# Sheet1.net
KiCad netlist of a schematic drawn in Altium Designer
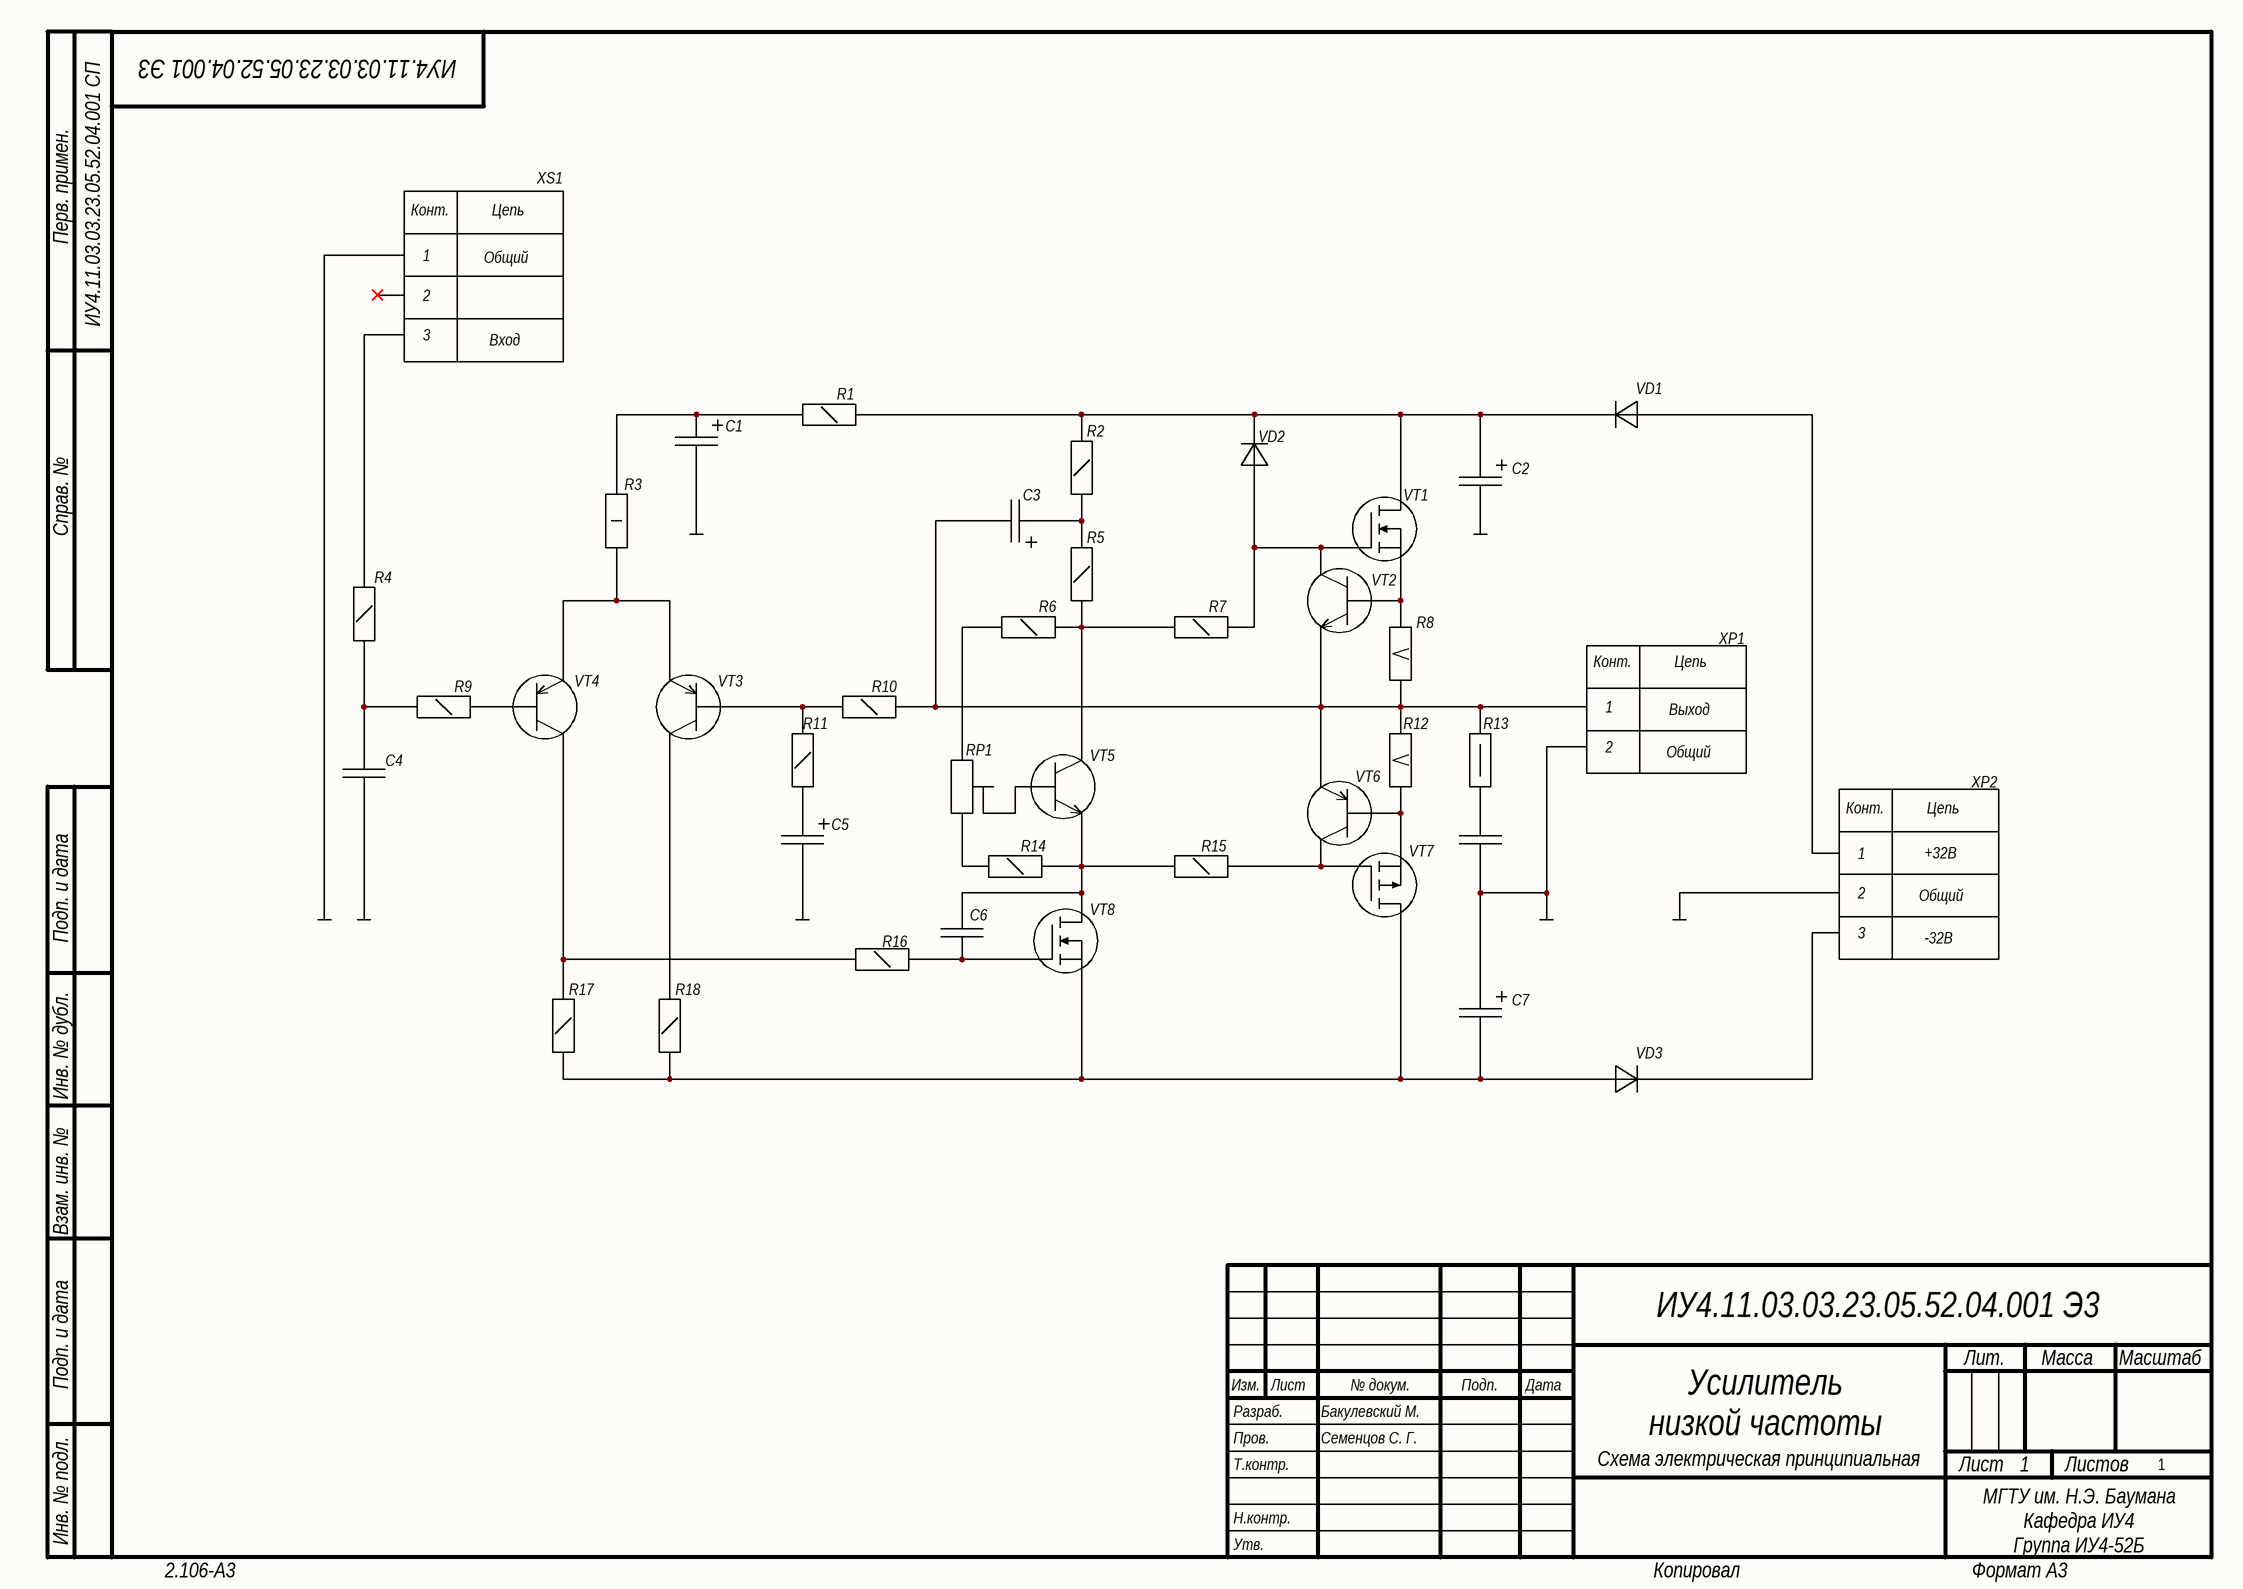
[diagram p0: Sheet1.SchDoc]

(export (version "E")
  (design (tool "Eeschema 10.0.6"))
  (components
    (comp (ref "C1")
      (value "2200uF 35V")
      (footprint "CAPPR350-800X700")
      (libsource (lib "Schlib1") (part "Cap Polarity 47uF 50V"))
    )
    (comp (ref "C2")
      (value "2200uF 35V")
      (footprint "CAPPR750-1600X3150")
      (libsource (lib "Schlib1") (part "Cap Polarity 2200uF 35V"))
    )
    (comp (ref "C3")
      (value "2200uF 35V")
      (footprint "CAPPR350-800X700")
      (libsource (lib "Schlib1") (part "Cap Polarity 47uF 50V"))
    )
    (comp (ref "C4")
      (value "Cap Ceramic 100pF")
      (footprint "CAPRR508-350X500X500")
      (libsource (lib "Schlib1") (part "Cap Ceramic 100pF"))
    )
    (comp (ref "C5")
      (value "100uF 100V")
      (footprint "CAPPR500-1000X2050")
      (libsource (lib "Schlib1") (part "Cap Polarity 100uF 100V"))
    )
    (comp (ref "C6")
      (value "Cap Ceramic 100pF")
      (footprint "CAPRR508-350X500X500")
      (libsource (lib "Schlib1") (part "Cap Ceramic 100pF"))
    )
    (comp (ref "C7")
      (value "2200uF 35V")
      (footprint "CAPPR750-1600X3150")
      (libsource (lib "Schlib1") (part "Cap Polarity 2200uF 35V"))
    )
    (comp (ref "https://www.eetimes.com/ic-audio-power-amplifiers-and-zobel-networks-one-size-does-not-fit-all/1")
      (value "2200uF 35V")
      (footprint "CAPR1000-400X1300X950")
      (libsource (lib "Schlib1") (part "Cap Film 0.68uF 250V"))
    )
    (comp (ref "R1")
      (value "Resistor 0.25W")
      (footprint "RES1016-630X250")
      (libsource (lib "Schlib1") (part "Resistor 0.25W"))
    )
    (comp (ref "R2")
      (value "Resistor 0.25W")
      (footprint "RES1016-630X250")
      (libsource (lib "Schlib1") (part "Resistor 0.25W"))
    )
    (comp (ref "R3")
      (value "Resistor 1W")
      (footprint "RES1651-1000X390")
      (libsource (lib "") (part "Resistor 1W_1"))
    )
    (comp (ref "R4")
      (value "Resistor 0.25W")
      (footprint "RES1016-630X250")
      (libsource (lib "Schlib1") (part "Resistor 0.25W"))
    )
    (comp (ref "R5")
      (value "Resistor 0.25W")
      (footprint "RES1016-630X250")
      (libsource (lib "Schlib1") (part "Resistor 0.25W"))
    )
    (comp (ref "R6")
      (value "Resistor 0.25W")
      (footprint "RES1016-630X250")
      (libsource (lib "Schlib1") (part "Resistor 0.25W"))
    )
    (comp (ref "R7")
      (value "Resistor 0.25W")
      (footprint "RES1016-630X250")
      (libsource (lib "Schlib1") (part "Resistor 0.25W"))
    )
    (comp (ref "R8")
      (value "Resistor 5W")
      (footprint "RES_5W")
      (libsource (lib "Schlib1") (part "Resistor 5W"))
    )
    (comp (ref "R9")
      (value "Resistor 0.25W")
      (footprint "RES1016-630X250")
      (libsource (lib "Schlib1") (part "Resistor 0.25W"))
    )
    (comp (ref "R10")
      (value "Resistor 0.25W")
      (footprint "RES1016-630X250")
      (libsource (lib "Schlib1") (part "Resistor 0.25W"))
    )
    (comp (ref "R11")
      (value "Resistor 0.25W")
      (footprint "RES1016-630X250")
      (libsource (lib "Schlib1") (part "Resistor 0.25W"))
    )
    (comp (ref "R12")
      (value "Resistor 5W")
      (footprint "RES_5W")
      (libsource (lib "Schlib1") (part "Resistor 5W"))
    )
    (comp (ref "R13")
      (value "Resistor 1W")
      (footprint "RES1651-1000X390")
      (libsource (lib "Schlib1") (part "Resistor 1W"))
    )
    (comp (ref "R14")
      (value "Resistor 0.25W")
      (footprint "RES1016-630X250")
      (libsource (lib "Schlib1") (part "Resistor 0.25W"))
    )
    (comp (ref "R15")
      (value "Resistor 0.25W")
      (footprint "RES1016-630X250")
      (libsource (lib "Schlib1") (part "Resistor 0.25W"))
    )
    (comp (ref "R16")
      (value "Resistor 0.25W")
      (footprint "RES1016-630X250")
      (libsource (lib "Schlib1") (part "Resistor 0.25W"))
    )
    (comp (ref "R17")
      (value "Resistor 0.25W")
      (footprint "RES1016-630X250")
      (libsource (lib "Schlib1") (part "Resistor 0.25W"))
    )
    (comp (ref "R18")
      (value "Resistor 0.25W")
      (footprint "RES1016-630X250")
      (libsource (lib "Schlib1") (part "Resistor 0.25W"))
    )
    (comp (ref "RP1")
      (value "~")
      (footprint "TRIM_BOURNS_3296W")
      (fields
        (field (name "MANUFACTURER") "Bourns")
        (field (name "PARTNUMBER") "3296W-1-103LF")
        (field (name "VALUEMANUFACTURERPARTNUMBER") "Resistor film, , , 3296W, 0.5W, -55...+125°C")
      )
      (libsource (lib "Schlib1") (part "Resistor Trimmer 1K"))
    )
    (comp (ref "VD1")
      (value "Diode 15SQ045")
      (footprint "R6")
      (fields (field (name "PUBLISHER") "Andrew Danich"))
      (libsource (lib "Schlib1") (part "Diode 15SQ045"))
    )
    (comp (ref "VD2")
      (value "Diode 1N4002")
      (footprint "DO-41")
      (fields (field (name "PUBLISHER") "Andrew Danich"))
      (libsource (lib "Schlib1") (part "Diode 1N4002"))
    )
    (comp (ref "VD3")
      (value "Diode 15SQ045")
      (footprint "R6")
      (fields (field (name "PUBLISHER") "Andrew Danich"))
      (libsource (lib "Schlib1") (part "Diode 15SQ045"))
    )
    (comp (ref "VT1") (value "~") (footprint "TO-220AB") (libsource (lib "Schlib1") (part "IRF510PBF")))
    (comp (ref "VT2") (value "BC546C") (footprint "TO-92-A") (libsource (lib "Schlib1") (part "BC546C")))
    (comp (ref "VT3") (value "BC556B") (footprint "TO-92-A") (libsource (lib "Schlib1") (part "BC556B")))
    (comp (ref "VT4") (value "BC556B") (footprint "TO-92-A") (libsource (lib "Schlib1") (part "BC556B")))
    (comp (ref "VT5")
      (value "Transistor NPN BC546C")
      (footprint "TO-92-A")
      (libsource (lib "Schlib1") (part "Transistor NPN BC546C"))
    )
    (comp (ref "VT6") (value "BC556B") (footprint "TO-92-A") (libsource (lib "Schlib1") (part "BC556B")))
    (comp (ref "VT7")
      (value "IRF9510PBF")
      (footprint "TO-220AB")
      (libsource (lib "Schlib1") (part "IRF9510PBF"))
    )
    (comp (ref "VT8")
      (value "~")
      (footprint "TO-92-A")
      (libsource (lib "Schlib1") (part "Transistor N-Mosfet BS170"))
    )
    (comp (ref "XP1")
      (value "Connector Dynamic 2 pin")
      (footprint "15EDGRC-3.81-02P")
      (libsource (lib "Schlib1") (part "Connector Dynamic 2 pin"))
    )
    (comp (ref "XP2")
      (value "Общий")
      (footprint "15EDGRC-3.81-03P")
      (libsource (lib "Schlib1") (part "Connector Power 3 pin"))
    )
    (comp (ref "XS1")
      (value "Общий")
      (footprint "ST-025")
      (libsource (lib "Schlib1") (part "Connector Audio 3 pin"))
    )
  )
  (nets
    (net (code "1") (name "GND") (class "Default")
      (node (ref "C1") (pin "2") (pinfunction "2_2") (pintype "passive"))
      (node (ref "C2") (pin "2") (pinfunction "2_2") (pintype "passive"))
      (node (ref "C4") (pin "2") (pinfunction "2_2") (pintype "passive"))
      (node (ref "C5") (pin "2") (pinfunction "2_2") (pintype "passive"))
      (node (ref "C7") (pin "1") (pinfunction "1_1") (pintype "passive"))
      (node (ref "XP1") (pin "2") (pinfunction "2_2") (pintype "passive"))
      (node (ref "XP2") (pin "2") (pinfunction "2_2") (pintype "passive"))
      (node (ref "XS1") (pin "1") (pinfunction "1_1") (pintype "passive"))
      (node (ref "https://www.eetimes.com/ic-audio-power-amplifiers-and-zobel-networks-one-size-does-not-fit-all/1") (pin "2") (pinfunction "2_2") (pintype "passive"))
    )
    (net (code "2") (name "Net-(C1-Pad1)") (class "Default")
      (node (ref "C1") (pin "1") (pinfunction "1_1") (pintype "passive"))
      (node (ref "R1") (pin "1") (pinfunction "1_1") (pintype "passive"))
      (node (ref "R3") (pin "1") (pinfunction "1_1") (pintype "passive"))
    )
    (net (code "3") (name "Net-(C3-Pad1)") (class "Default")
      (node (ref "C3") (pin "1") (pinfunction "1_1") (pintype "passive"))
      (node (ref "R2") (pin "1") (pinfunction "1_1") (pintype "passive"))
      (node (ref "R5") (pin "2") (pinfunction "2_2") (pintype "passive"))
    )
    (net (code "4") (name "Net-(C4-Pad1)") (class "Default")
      (node (ref "C4") (pin "1") (pinfunction "1_1") (pintype "passive"))
      (node (ref "R4") (pin "1") (pinfunction "1_1") (pintype "passive"))
      (node (ref "R9") (pin "1") (pinfunction "1_1") (pintype "passive"))
    )
    (net (code "5") (name "Net-(C5-Pad1)") (class "Default")
      (node (ref "C5") (pin "1") (pinfunction "1_1") (pintype "passive"))
      (node (ref "R11") (pin "2") (pinfunction "2_2") (pintype "passive"))
    )
    (net (code "6") (name "Net-(R4-Pad2)") (class "Default")
      (node (ref "R4") (pin "2") (pinfunction "2_2") (pintype "passive"))
      (node (ref "XS1") (pin "3") (pinfunction "3_3") (pintype "passive"))
    )
    (net (code "7") (name "Net-(R6-Pad1)") (class "Default")
      (node (ref "R6") (pin "1") (pinfunction "1_1") (pintype "passive"))
      (node (ref "RP1") (pin "1") (pinfunction "1_1") (pintype "passive"))
    )
    (net (code "8") (name "Net-(R13-Pad1)") (class "Default")
      (node (ref "R13") (pin "1") (pinfunction "1_1") (pintype "passive"))
      (node (ref "https://www.eetimes.com/ic-audio-power-amplifiers-and-zobel-networks-one-size-does-not-fit-all/1") (pin "1") (pinfunction "1_1") (pintype "passive"))
    )
    (net (code "9") (name "Net-(R14-Pad2)") (class "Default")
      (node (ref "R14") (pin "2") (pinfunction "2_2") (pintype "passive"))
      (node (ref "RP1") (pin "3") (pinfunction "3_3") (pintype "passive"))
    )
    (net (code "10") (name "Net-(VD1-А)") (class "Default")
      (node (ref "VD1") (pin "1") (pinfunction "А_1") (pintype "passive"))
      (node (ref "XP2") (pin "1") (pinfunction "1_1") (pintype "passive"))
    )
    (net (code "11") (name "Net-(VD1-К)") (class "Default")
      (node (ref "C2") (pin "1") (pinfunction "1_1") (pintype "passive"))
      (node (ref "R1") (pin "2") (pinfunction "2_2") (pintype "passive"))
      (node (ref "R2") (pin "2") (pinfunction "2_2") (pintype "passive"))
      (node (ref "VD1") (pin "2") (pinfunction "К_2") (pintype "passive"))
      (node (ref "VD2") (pin "2") (pinfunction "К_2") (pintype "passive"))
      (node (ref "VT1") (pin "2") (pinfunction "D_2") (pintype "passive"))
    )
    (net (code "12") (name "Net-(VD2-А)") (class "Default")
      (node (ref "R7") (pin "2") (pinfunction "2_2") (pintype "passive"))
      (node (ref "VD2") (pin "1") (pinfunction "А_1") (pintype "passive"))
      (node (ref "VT1") (pin "1") (pinfunction "G_1") (pintype "passive"))
      (node (ref "VT2") (pin "1") (pinfunction "К_1") (pintype "passive"))
    )
    (net (code "13") (name "Net-(VD3-А)") (class "Default")
      (node (ref "C7") (pin "2") (pinfunction "2_2") (pintype "passive"))
      (node (ref "R17") (pin "1") (pinfunction "1_1") (pintype "passive"))
      (node (ref "R18") (pin "1") (pinfunction "1_1") (pintype "passive"))
      (node (ref "VD3") (pin "1") (pinfunction "А_1") (pintype "passive"))
      (node (ref "VT7") (pin "2") (pinfunction "D_2") (pintype "passive"))
      (node (ref "VT8") (pin "3") (pinfunction "S_3") (pintype "passive"))
    )
    (net (code "14") (name "Net-(VD3-К)") (class "Default")
      (node (ref "VD3") (pin "2") (pinfunction "К_2") (pintype "passive"))
      (node (ref "XP2") (pin "3") (pinfunction "3_3") (pintype "passive"))
    )
    (net (code "15") (name "Net-(VT1-S)") (class "Default")
      (node (ref "R8") (pin "2") (pinfunction "2_2") (pintype "passive"))
      (node (ref "VT1") (pin "3") (pinfunction "S_3") (pintype "passive"))
      (node (ref "VT2") (pin "2") (pinfunction "Б_2") (pintype "passive"))
    )
    (net (code "16") (name "Net-(VT2-Э)") (class "Default")
      (node (ref "C3") (pin "2") (pinfunction "2_2") (pintype "passive"))
      (node (ref "R10") (pin "2") (pinfunction "2_2") (pintype "passive"))
      (node (ref "R12") (pin "2") (pinfunction "2_2") (pintype "passive"))
      (node (ref "R13") (pin "2") (pinfunction "2_2") (pintype "passive"))
      (node (ref "R8") (pin "1") (pinfunction "1_1") (pintype "passive"))
      (node (ref "VT2") (pin "3") (pinfunction "Э_3") (pintype "passive"))
      (node (ref "VT6") (pin "3") (pinfunction "Э_3") (pintype "passive"))
      (node (ref "XP1") (pin "1") (pinfunction "1_1") (pintype "passive"))
    )
    (net (code "17") (name "Net-(VT3-Б)") (class "Default")
      (node (ref "R10") (pin "1") (pinfunction "1_1") (pintype "passive"))
      (node (ref "R11") (pin "1") (pinfunction "1_1") (pintype "passive"))
      (node (ref "VT3") (pin "2") (pinfunction "Б_2") (pintype "passive"))
    )
    (net (code "18") (name "Net-(VT3-К)") (class "Default")
      (node (ref "R18") (pin "2") (pinfunction "2_2") (pintype "passive"))
      (node (ref "VT3") (pin "1") (pinfunction "К_1") (pintype "passive"))
    )
    (net (code "19") (name "Net-(VT3-Э)") (class "Default")
      (node (ref "R3") (pin "2") (pinfunction "2_2") (pintype "passive"))
      (node (ref "VT3") (pin "3") (pinfunction "Э_3") (pintype "passive"))
      (node (ref "VT4") (pin "3") (pinfunction "Э_3") (pintype "passive"))
    )
    (net (code "20") (name "Net-(VT4-Б)") (class "Default")
      (node (ref "R9") (pin "2") (pinfunction "2_2") (pintype "passive"))
      (node (ref "VT4") (pin "2") (pinfunction "Б_2") (pintype "passive"))
    )
    (net (code "21") (name "Net-(VT4-К)") (class "Default")
      (node (ref "R16") (pin "2") (pinfunction "2_2") (pintype "passive"))
      (node (ref "R17") (pin "2") (pinfunction "2_2") (pintype "passive"))
      (node (ref "VT4") (pin "1") (pinfunction "К_1") (pintype "passive"))
    )
    (net (code "22") (name "Net-(VT5-Б)") (class "Default")
      (node (ref "RP1") (pin "2") (pinfunction "2_2") (pintype "passive"))
      (node (ref "VT5") (pin "2") (pinfunction "Б_2") (pintype "passive"))
    )
    (net (code "23") (name "Net-(VT5-К)") (class "Default")
      (node (ref "R5") (pin "1") (pinfunction "1_1") (pintype "passive"))
      (node (ref "R6") (pin "2") (pinfunction "2_2") (pintype "passive"))
      (node (ref "R7") (pin "1") (pinfunction "1_1") (pintype "passive"))
      (node (ref "VT5") (pin "1") (pinfunction "К_1") (pintype "passive"))
    )
    (net (code "24") (name "Net-(VT5-Э)") (class "Default")
      (node (ref "C6") (pin "2") (pinfunction "2_2") (pintype "passive"))
      (node (ref "R14") (pin "1") (pinfunction "1_1") (pintype "passive"))
      (node (ref "R15") (pin "1") (pinfunction "1_1") (pintype "passive"))
      (node (ref "VT5") (pin "3") (pinfunction "Э_3") (pintype "passive"))
      (node (ref "VT8") (pin "1") (pinfunction "D_1") (pintype "passive"))
    )
    (net (code "25") (name "Net-(VT6-Б)") (class "Default")
      (node (ref "R12") (pin "1") (pinfunction "1_1") (pintype "passive"))
      (node (ref "VT6") (pin "2") (pinfunction "Б_2") (pintype "passive"))
      (node (ref "VT7") (pin "3") (pinfunction "S_3") (pintype "passive"))
    )
    (net (code "26") (name "Net-(VT6-К)") (class "Default")
      (node (ref "R15") (pin "2") (pinfunction "2_2") (pintype "passive"))
      (node (ref "VT6") (pin "1") (pinfunction "К_1") (pintype "passive"))
      (node (ref "VT7") (pin "1") (pinfunction "G_1") (pintype "passive"))
    )
    (net (code "27") (name "Net-(VT8-G)") (class "Default")
      (node (ref "C6") (pin "1") (pinfunction "1_1") (pintype "passive"))
      (node (ref "R16") (pin "1") (pinfunction "1_1") (pintype "passive"))
      (node (ref "VT8") (pin "2") (pinfunction "G_2") (pintype "passive"))
    )
    (net (code "28") (name "unconnected-(XS1-Pad2)") (class "Default")
      (node (ref "XS1") (pin "2") (pinfunction "2_2") (pintype "passive+no_connect"))
    )
  )
)
